# otb-8266.net
KiCad netlist of a schematic drawn in EAGLE
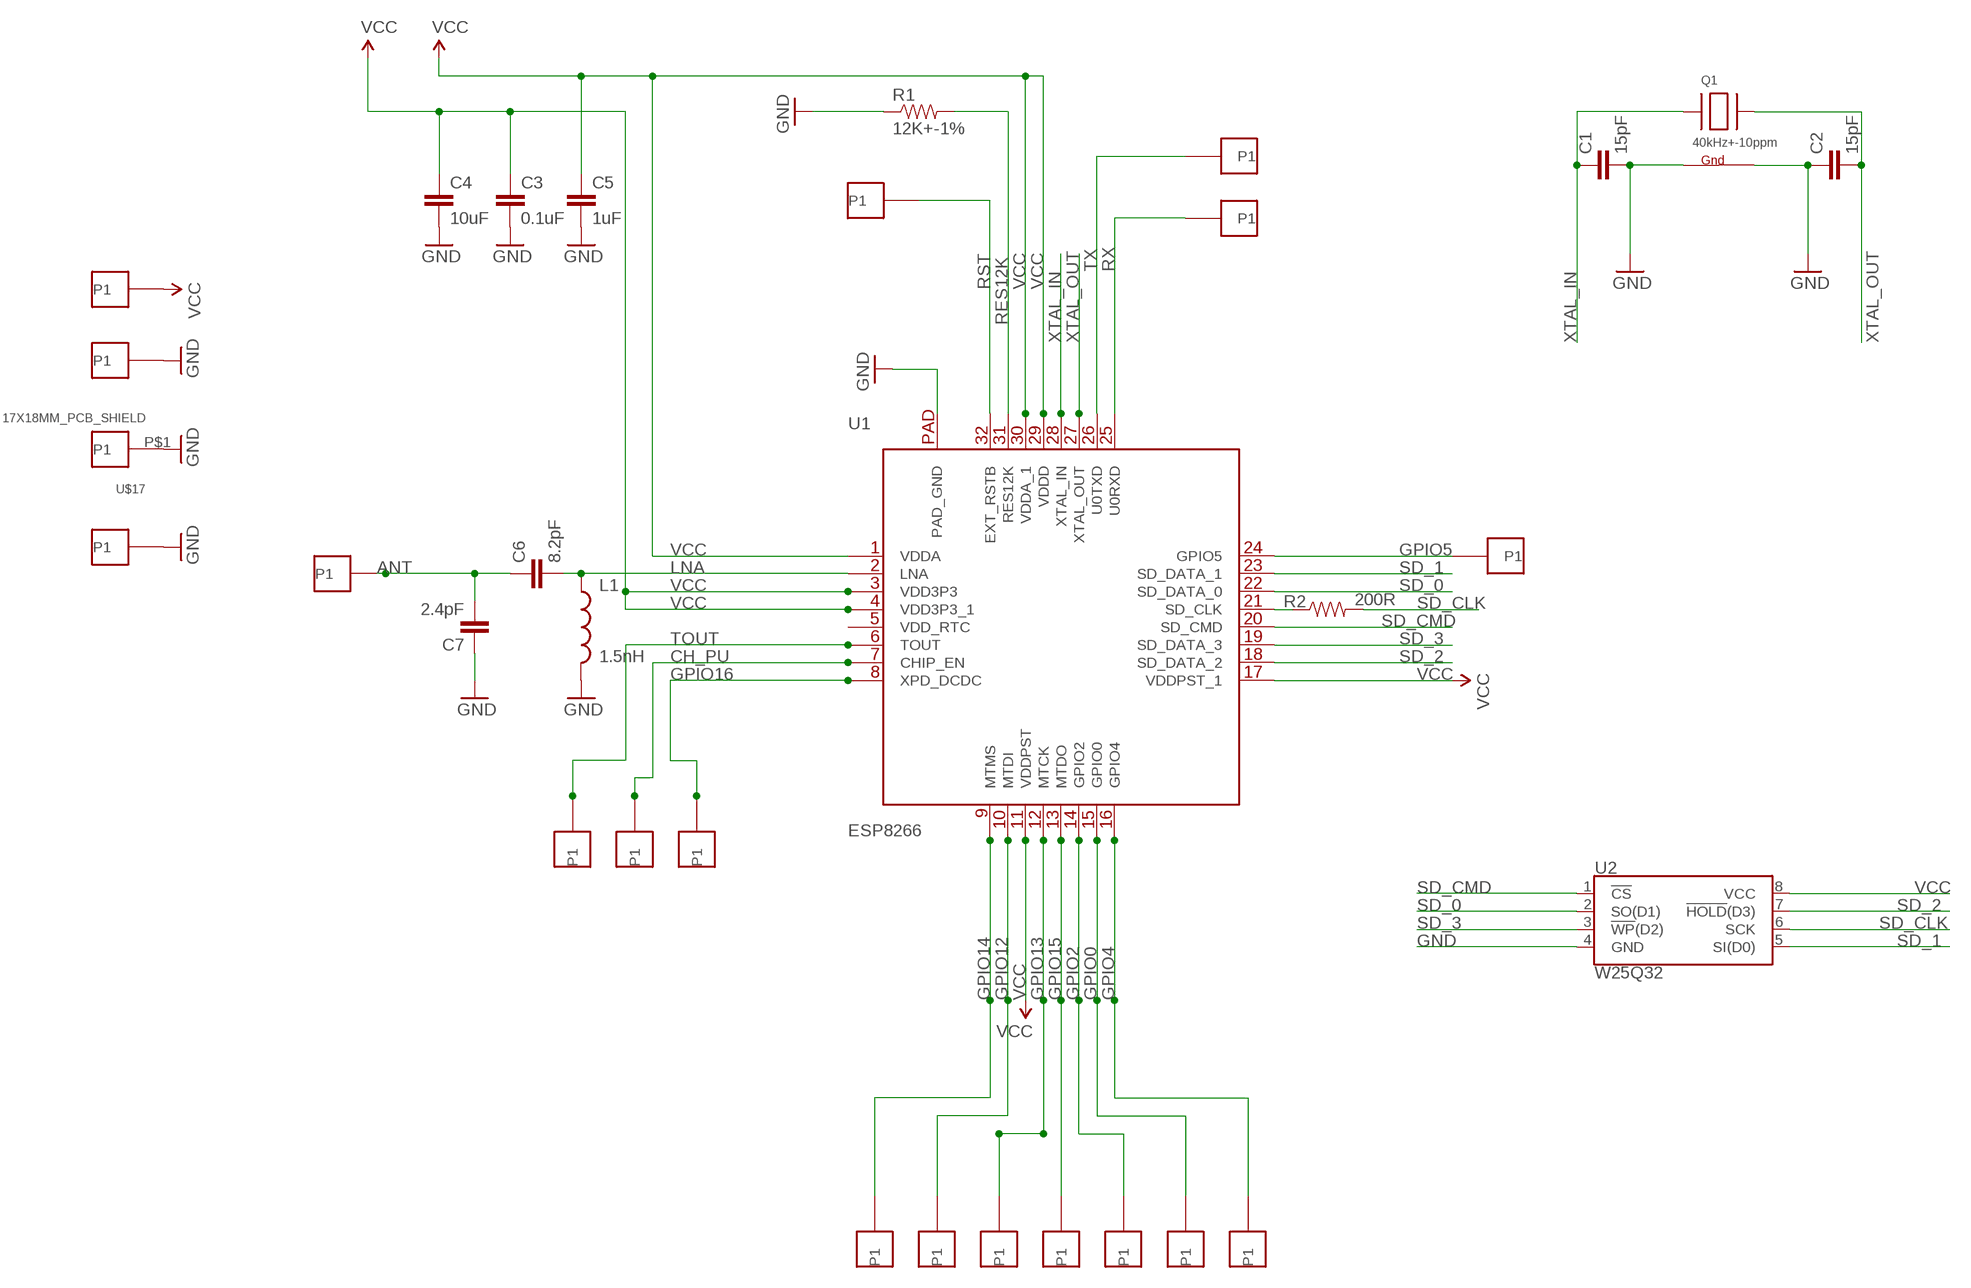
[diagram p0: schematic, sheet 1]

(export (version "E")
  (design (tool "Eeschema 10.0.6"))
  (components
    (comp (ref "C1")
      (value "15pF")
      (footprint "eagle-import:0402-CAP")
      (libsource (lib "eagle-import") (part "SparkFun-Passives_CAP0402-CAP"))
    )
    (comp (ref "C2")
      (value "15pF")
      (footprint "eagle-import:0402-CAP")
      (libsource (lib "eagle-import") (part "SparkFun-Passives_CAP0402-CAP"))
    )
    (comp (ref "C3")
      (value "0.1uF")
      (footprint "eagle-import:0402-CAP")
      (libsource (lib "eagle-import") (part "SparkFun-Passives_CAP0402-CAP"))
    )
    (comp (ref "C4")
      (value "10uF")
      (footprint "eagle-import:0603-CAP")
      (libsource (lib "eagle-import") (part "CAP0603-CAP"))
    )
    (comp (ref "C5")
      (value "1uF")
      (footprint "eagle-import:0603-CAP")
      (libsource (lib "eagle-import") (part "CAP0603-CAP"))
    )
    (comp (ref "C6")
      (value "8.2pF")
      (footprint "eagle-import:0402-CAP")
      (libsource (lib "eagle-import") (part "SparkFun-Passives_CAP0402-CAP"))
    )
    (comp (ref "C7")
      (value "2.4pF")
      (footprint "eagle-import:0402-CAP")
      (libsource (lib "eagle-import") (part "SparkFun-Passives_CAP0402-CAP"))
    )
    (comp (ref "L1")
      (value "1.5nH")
      (footprint "eagle-import:C0402")
      (libsource (lib "eagle-import") (part "INDUCTOR0402"))
    )
    (comp (ref "Q1")
      (value "40kHz+-10ppm")
      (footprint "eagle-import:NX3225")
      (libsource (lib "eagle-import") (part "XTAL-4-3225"))
    )
    (comp (ref "R1")
      (value "12K+-1%")
      (footprint "eagle-import:0402-RES")
      (libsource (lib "eagle-import") (part "RESISTOR0402-RES"))
    )
    (comp (ref "R2")
      (value "200R")
      (footprint "eagle-import:0402-RES")
      (libsource (lib "eagle-import") (part "RESISTOR0402-RES"))
    )
    (comp (ref "U$1")
      (value "1.27MM_PITCH_PLATED_HOLE")
      (footprint "eagle-import:1.27MM_PITCH_PLATED_HOLE")
      (libsource (lib "eagle-import") (part "1.27MM_PITCH_PLATED_HOLE"))
    )
    (comp (ref "U$2")
      (value "1.27MM_PITCH_PLATED_HOLE")
      (footprint "eagle-import:1.27MM_PITCH_PLATED_HOLE")
      (libsource (lib "eagle-import") (part "1.27MM_PITCH_PLATED_HOLE"))
    )
    (comp (ref "U$3")
      (value "1.27MM_PITCH_PLATED_HOLE")
      (footprint "eagle-import:1.27MM_PITCH_PLATED_HOLE")
      (libsource (lib "eagle-import") (part "1.27MM_PITCH_PLATED_HOLE"))
    )
    (comp (ref "U$4")
      (value "1.27MM_PITCH_PLATED_HOLE")
      (footprint "eagle-import:1.27MM_PITCH_PLATED_HOLE")
      (libsource (lib "eagle-import") (part "1.27MM_PITCH_PLATED_HOLE"))
    )
    (comp (ref "U$5")
      (value "1.27MM_PITCH_PLATED_HOLE")
      (footprint "eagle-import:1.27MM_PITCH_PLATED_HOLE")
      (libsource (lib "eagle-import") (part "1.27MM_PITCH_PLATED_HOLE"))
    )
    (comp (ref "U$6")
      (value "1.27MM_PITCH_PLATED_HOLE")
      (footprint "eagle-import:1.27MM_PITCH_PLATED_HOLE")
      (libsource (lib "eagle-import") (part "1.27MM_PITCH_PLATED_HOLE"))
    )
    (comp (ref "U$7")
      (value "1.27MM_PITCH_PLATED_HOLE")
      (footprint "eagle-import:1.27MM_PITCH_PLATED_HOLE")
      (libsource (lib "eagle-import") (part "1.27MM_PITCH_PLATED_HOLE"))
    )
    (comp (ref "U$8")
      (value "1.27MM_PITCH_PLATED_HOLE")
      (footprint "eagle-import:1.27MM_PITCH_PLATED_HOLE")
      (libsource (lib "eagle-import") (part "1.27MM_PITCH_PLATED_HOLE"))
    )
    (comp (ref "U$9")
      (value "1.27MM_PITCH_PLATED_HOLE")
      (footprint "eagle-import:1.27MM_PITCH_PLATED_HOLE")
      (libsource (lib "eagle-import") (part "1.27MM_PITCH_PLATED_HOLE"))
    )
    (comp (ref "U$10")
      (value "1.27MM_PITCH_PLATED_HOLE")
      (footprint "eagle-import:1.27MM_PITCH_PLATED_HOLE")
      (libsource (lib "eagle-import") (part "1.27MM_PITCH_PLATED_HOLE"))
    )
    (comp (ref "U$11")
      (value "1.27MM_PITCH_PLATED_HOLE")
      (footprint "eagle-import:1.27MM_PITCH_PLATED_HOLE")
      (libsource (lib "eagle-import") (part "1.27MM_PITCH_PLATED_HOLE"))
    )
    (comp (ref "U$12")
      (value "1.27MM_PITCH_PLATED_HOLE")
      (footprint "eagle-import:1.27MM_PITCH_PLATED_HOLE")
      (libsource (lib "eagle-import") (part "1.27MM_PITCH_PLATED_HOLE"))
    )
    (comp (ref "U$13")
      (value "1.27MM_PITCH_PLATED_HOLE")
      (footprint "eagle-import:1.27MM_PITCH_PLATED_HOLE")
      (libsource (lib "eagle-import") (part "1.27MM_PITCH_PLATED_HOLE"))
    )
    (comp (ref "U$14")
      (value "1.27MM_PITCH_PLATED_HOLE")
      (footprint "eagle-import:1.27MM_PITCH_PLATED_HOLE")
      (libsource (lib "eagle-import") (part "1.27MM_PITCH_PLATED_HOLE"))
    )
    (comp (ref "U$15")
      (value "1.27MM_PITCH_PLATED_HOLE")
      (footprint "eagle-import:1.27MM_PITCH_PLATED_HOLE")
      (libsource (lib "eagle-import") (part "1.27MM_PITCH_PLATED_HOLE"))
    )
    (comp (ref "U$16")
      (value "1.27MM_PITCH_PLATED_HOLE")
      (footprint "eagle-import:1.27MM_PITCH_PLATED_HOLE")
      (libsource (lib "eagle-import") (part "1.27MM_PITCH_PLATED_HOLE"))
    )
    (comp (ref "U$17")
      (value "17X18MM_PCB_SHIELD")
      (footprint "eagle-import:17X18_SHIELD")
      (libsource (lib "eagle-import") (part "17X18MM_PCB_SHIELD"))
    )
    (comp (ref "U$18")
      (value "1.27MM_PITCH_PLATED_HOLE")
      (footprint "eagle-import:1.27MM_PITCH_PLATED_HOLE")
      (libsource (lib "eagle-import") (part "1.27MM_PITCH_PLATED_HOLE"))
    )
    (comp (ref "U$19")
      (value "1.27MM_PITCH_PLATED_HOLE")
      (footprint "eagle-import:1.27MM_PITCH_PLATED_HOLE")
      (libsource (lib "eagle-import") (part "1.27MM_PITCH_PLATED_HOLE"))
    )
    (comp (ref "U1")
      (value "ESP8266")
      (footprint "eagle-import:QFN32")
      (libsource (lib "eagle-import") (part "ESP8266"))
    )
    (comp (ref "U2")
      (value "W25Q32")
      (footprint "eagle-import:SOIC-8")
      (libsource (lib "eagle-import") (part "W25Q32FVSS"))
    )
  )
  (nets
    (net (code "1") (name "/ANT") (class "Default")
      (node (ref "C6") (pin "1") (pinfunction "1_1") (pintype "passive"))
      (node (ref "C7") (pin "2") (pinfunction "2_2") (pintype "passive"))
      (node (ref "U$16") (pin "P1") (pinfunction "P1_P1") (pintype "bidirectional"))
    )
    (net (code "2") (name "/CH_PU") (class "Default")
      (node (ref "U$4") (pin "P1") (pinfunction "P1_P1") (pintype "bidirectional"))
      (node (ref "U1") (pin "7") (pinfunction "CHIP_EN_7") (pintype "bidirectional"))
    )
    (net (code "3") (name "/GPIO0") (class "Default")
      (node (ref "U$11") (pin "P1") (pinfunction "P1_P1") (pintype "bidirectional"))
      (node (ref "U1") (pin "15") (pinfunction "GPIO0_15") (pintype "bidirectional"))
    )
    (net (code "4") (name "/GPIO2") (class "Default")
      (node (ref "U$10") (pin "P1") (pinfunction "P1_P1") (pintype "bidirectional"))
      (node (ref "U1") (pin "14") (pinfunction "GPIO2_14") (pintype "bidirectional"))
    )
    (net (code "5") (name "/GPIO4") (class "Default")
      (node (ref "U$12") (pin "P1") (pinfunction "P1_P1") (pintype "bidirectional"))
      (node (ref "U1") (pin "16") (pinfunction "GPIO4_16") (pintype "bidirectional"))
    )
    (net (code "6") (name "/GPIO5") (class "Default")
      (node (ref "U$18") (pin "P1") (pinfunction "P1_P1") (pintype "bidirectional"))
      (node (ref "U1") (pin "24") (pinfunction "GPIO5_24") (pintype "bidirectional"))
    )
    (net (code "7") (name "/GPIO12") (class "Default")
      (node (ref "U$7") (pin "P1") (pinfunction "P1_P1") (pintype "bidirectional"))
      (node (ref "U1") (pin "10") (pinfunction "MTDI_10") (pintype "bidirectional"))
    )
    (net (code "8") (name "/GPIO13") (class "Default")
      (node (ref "U$8") (pin "P1") (pinfunction "P1_P1") (pintype "bidirectional"))
      (node (ref "U1") (pin "12") (pinfunction "MTCK_12") (pintype "bidirectional"))
    )
    (net (code "9") (name "/GPIO14") (class "Default")
      (node (ref "U$6") (pin "P1") (pinfunction "P1_P1") (pintype "bidirectional"))
      (node (ref "U1") (pin "9") (pinfunction "MTMS_9") (pintype "bidirectional"))
    )
    (net (code "10") (name "/GPIO15") (class "Default")
      (node (ref "U$9") (pin "P1") (pinfunction "P1_P1") (pintype "bidirectional"))
      (node (ref "U1") (pin "13") (pinfunction "MTDO_13") (pintype "bidirectional"))
    )
    (net (code "11") (name "/GPIO16") (class "Default")
      (node (ref "U$5") (pin "P1") (pinfunction "P1_P1") (pintype "bidirectional"))
      (node (ref "U1") (pin "8") (pinfunction "XPD_DCDC_8") (pintype "bidirectional"))
    )
    (net (code "12") (name "/LNA") (class "Default")
      (node (ref "C6") (pin "2") (pinfunction "2_2") (pintype "passive"))
      (node (ref "L1") (pin "1") (pinfunction "1_1") (pintype "passive"))
      (node (ref "U1") (pin "2") (pinfunction "LNA_2") (pintype "bidirectional"))
    )
    (net (code "13") (name "/RES12K") (class "Default")
      (node (ref "R1") (pin "2") (pinfunction "2_2") (pintype "passive"))
      (node (ref "U1") (pin "31") (pinfunction "RES12K_31") (pintype "bidirectional"))
    )
    (net (code "14") (name "/RST") (class "Default")
      (node (ref "U$15") (pin "P1") (pinfunction "P1_P1") (pintype "bidirectional"))
      (node (ref "U1") (pin "32") (pinfunction "EXT_RSTB_32") (pintype "bidirectional"))
    )
    (net (code "15") (name "/RX") (class "Default")
      (node (ref "U$13") (pin "P1") (pinfunction "P1_P1") (pintype "bidirectional"))
      (node (ref "U1") (pin "25") (pinfunction "U0RXD_25") (pintype "bidirectional"))
    )
    (net (code "16") (name "/SD_0") (class "Default")
      (node (ref "U1") (pin "22") (pinfunction "SD_DATA_0_22") (pintype "bidirectional"))
      (node (ref "U2") (pin "2") (pinfunction "SO(D1)_2") (pintype "bidirectional"))
    )
    (net (code "17") (name "/SD_1") (class "Default")
      (node (ref "U1") (pin "23") (pinfunction "SD_DATA_1_23") (pintype "bidirectional"))
      (node (ref "U2") (pin "5") (pinfunction "SI(D0)_5") (pintype "bidirectional"))
    )
    (net (code "18") (name "/SD_2") (class "Default")
      (node (ref "U1") (pin "18") (pinfunction "SD_DATA_2_18") (pintype "bidirectional"))
      (node (ref "U2") (pin "7") (pinfunction "~{HOLD}(D3)_7") (pintype "bidirectional"))
    )
    (net (code "19") (name "/SD_3") (class "Default")
      (node (ref "U1") (pin "19") (pinfunction "SD_DATA_3_19") (pintype "bidirectional"))
      (node (ref "U2") (pin "3") (pinfunction "~{WP}(D2)_3") (pintype "bidirectional"))
    )
    (net (code "20") (name "/SD_CLK") (class "Default")
      (node (ref "R2") (pin "2") (pinfunction "2_2") (pintype "passive"))
      (node (ref "U2") (pin "6") (pinfunction "SCK_6") (pintype "bidirectional"))
    )
    (net (code "21") (name "/SD_CMD") (class "Default")
      (node (ref "U1") (pin "20") (pinfunction "SD_CMD_20") (pintype "bidirectional"))
      (node (ref "U2") (pin "1") (pinfunction "~{CS}_1") (pintype "bidirectional"))
    )
    (net (code "22") (name "/TOUT") (class "Default")
      (node (ref "U$3") (pin "P1") (pinfunction "P1_P1") (pintype "bidirectional"))
      (node (ref "U1") (pin "6") (pinfunction "TOUT_6") (pintype "bidirectional"))
    )
    (net (code "23") (name "/TX") (class "Default")
      (node (ref "U$14") (pin "P1") (pinfunction "P1_P1") (pintype "bidirectional"))
      (node (ref "U1") (pin "26") (pinfunction "U0TXD_26") (pintype "bidirectional"))
    )
    (net (code "24") (name "/XTAL_IN") (class "Default")
      (node (ref "C1") (pin "1") (pinfunction "1_1") (pintype "passive"))
      (node (ref "Q1") (pin "1") (pinfunction "X1_1") (pintype "bidirectional"))
      (node (ref "U1") (pin "28") (pinfunction "XTAL_IN_28") (pintype "bidirectional"))
    )
    (net (code "25") (name "/XTAL_OUT") (class "Default")
      (node (ref "C2") (pin "2") (pinfunction "2_2") (pintype "passive"))
      (node (ref "Q1") (pin "3") (pinfunction "X2_3") (pintype "bidirectional"))
      (node (ref "U1") (pin "27") (pinfunction "XTAL_OUT_27") (pintype "bidirectional"))
    )
    (net (code "26") (name "GND") (class "Default")
      (node (ref "C1") (pin "2") (pinfunction "2_2") (pintype "passive"))
      (node (ref "C2") (pin "1") (pinfunction "1_1") (pintype "passive"))
      (node (ref "C3") (pin "2") (pinfunction "2_2") (pintype "passive"))
      (node (ref "C4") (pin "2") (pinfunction "2_2") (pintype "passive"))
      (node (ref "C5") (pin "2") (pinfunction "2_2") (pintype "passive"))
      (node (ref "C7") (pin "1") (pinfunction "1_1") (pintype "passive"))
      (node (ref "L1") (pin "2") (pinfunction "2_2") (pintype "passive"))
      (node (ref "Q1") (pin "2") (pinfunction "G2_2") (pintype "power_in"))
      (node (ref "Q1") (pin "4") (pinfunction "G1_4") (pintype "power_in"))
      (node (ref "R1") (pin "1") (pinfunction "1_1") (pintype "passive"))
      (node (ref "U$17") (pin "P$1") (pinfunction "P1_P$1") (pintype "bidirectional"))
      (node (ref "U$19") (pin "P1") (pinfunction "P1_P1") (pintype "bidirectional"))
      (node (ref "U$2") (pin "P1") (pinfunction "P1_P1") (pintype "bidirectional"))
      (node (ref "U1") (pin "EP") (pinfunction "PAD_GND_EP") (pintype "bidirectional"))
      (node (ref "U2") (pin "4") (pinfunction "GND_4") (pintype "bidirectional"))
    )
    (net (code "27") (name "Net-(U1-SD_CLK)") (class "Default")
      (node (ref "R2") (pin "1") (pinfunction "1_1") (pintype "passive"))
      (node (ref "U1") (pin "21") (pinfunction "SD_CLK_21") (pintype "bidirectional"))
    )
    (net (code "28") (name "VCC") (class "Default")
      (node (ref "C3") (pin "1") (pinfunction "1_1") (pintype "passive"))
      (node (ref "C4") (pin "1") (pinfunction "1_1") (pintype "passive"))
      (node (ref "C5") (pin "1") (pinfunction "1_1") (pintype "passive"))
      (node (ref "U$1") (pin "P1") (pinfunction "P1_P1") (pintype "bidirectional"))
      (node (ref "U1") (pin "1") (pinfunction "VDDA_1") (pintype "bidirectional"))
      (node (ref "U1") (pin "11") (pinfunction "VDDPST_11") (pintype "bidirectional"))
      (node (ref "U1") (pin "17") (pinfunction "VDDPST_1_17") (pintype "bidirectional"))
      (node (ref "U1") (pin "29") (pinfunction "VDDD_29") (pintype "bidirectional"))
      (node (ref "U1") (pin "3") (pinfunction "VDD3P3_3") (pintype "bidirectional"))
      (node (ref "U1") (pin "30") (pinfunction "VDDA_1_30") (pintype "bidirectional"))
      (node (ref "U1") (pin "4") (pinfunction "VDD3P3_1_4") (pintype "bidirectional"))
      (node (ref "U2") (pin "8") (pinfunction "VCC_8") (pintype "bidirectional"))
    )
    (net (code "29") (name "unconnected-(U1-VDD_RTC-Pad5)") (class "Default")
      (node (ref "U1") (pin "5") (pinfunction "VDD_RTC_5") (pintype "bidirectional"))
    )
  )
)
